# STM32_Schemaic.net
KiCad netlist of a schematic drawn in Altium Designer
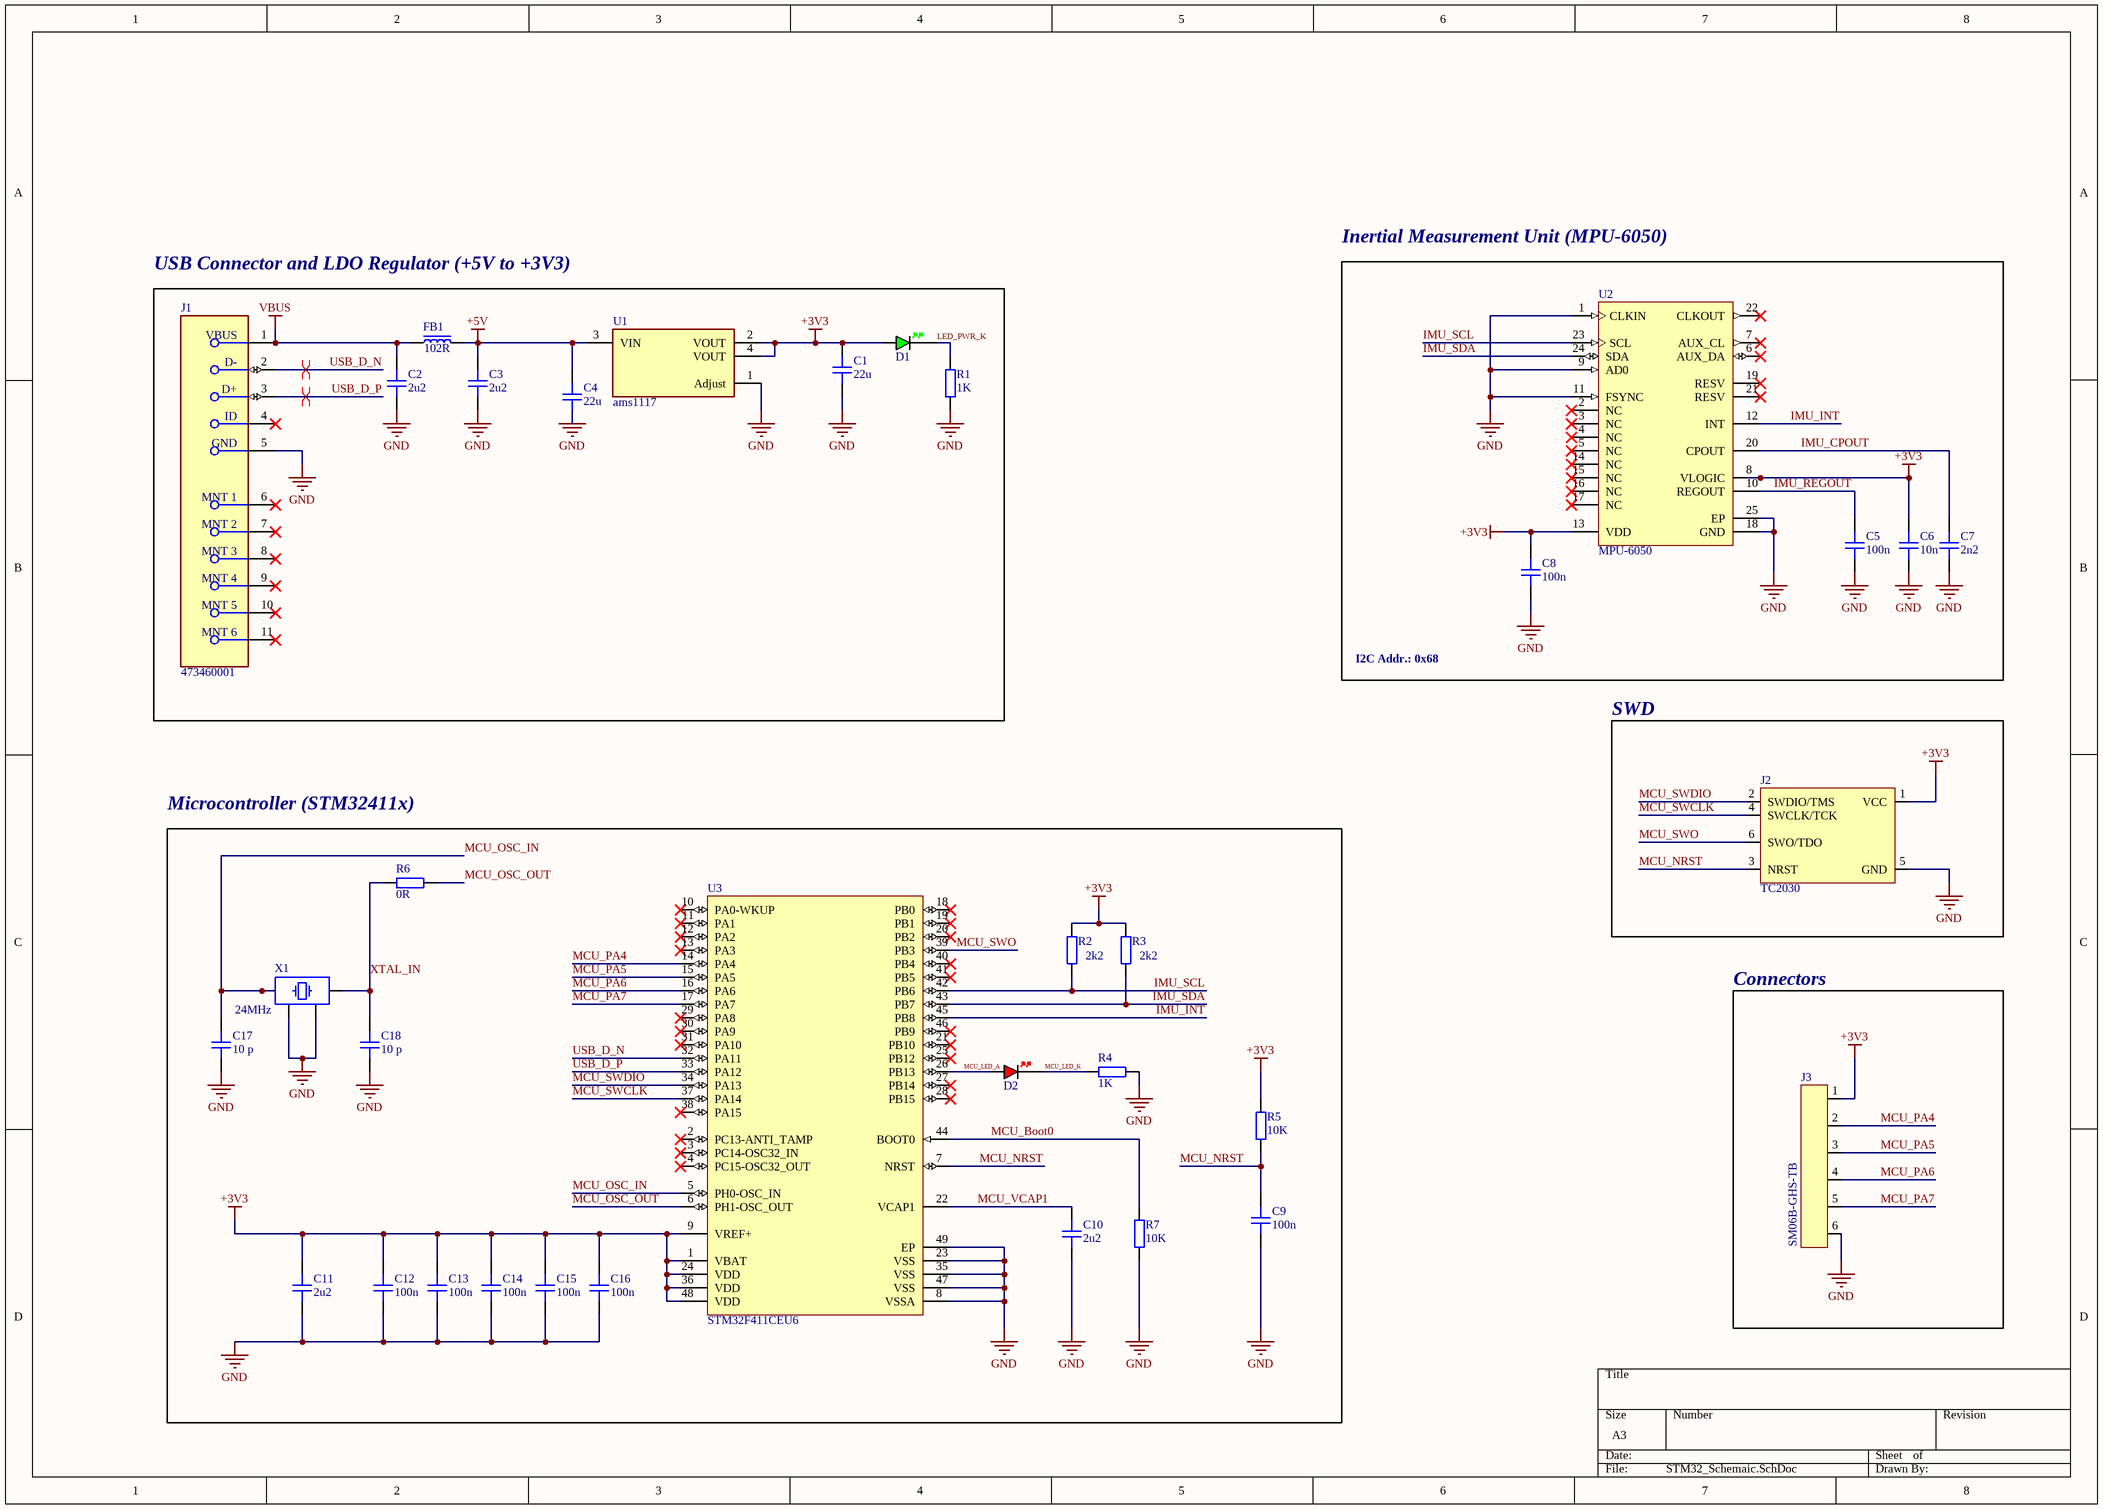
[diagram p0: STM32_Schemaic.SchDoc]

(export (version "E")
  (design (tool "Eeschema 10.0.6"))
  (components
    (comp (ref "C1")
      (value "22u")
      (footprint "CAP_0805")
      (description "Capacitor SMD 0805")
      (libsource (lib "Schematic-Lib-PhilsLab") (part "CAP_0805"))
    )
    (comp (ref "C2")
      (value "2u2")
      (footprint "CAP_0603")
      (description "Capacitor SMD 0603")
      (libsource (lib "Schematic-Lib-PhilsLab") (part "CAP_0603"))
    )
    (comp (ref "C3")
      (value "2u2")
      (footprint "CAP_0603")
      (description "Capacitor SMD 0603")
      (libsource (lib "Schematic-Lib-PhilsLab") (part "CAP_0603"))
    )
    (comp (ref "C4")
      (value "22u")
      (footprint "CAP_0805")
      (description "Capacitor SMD 0805")
      (libsource (lib "Schematic-Lib-PhilsLab") (part "CAP_0805"))
    )
    (comp (ref "C5")
      (value "100n")
      (footprint "CAP_0402")
      (description "Capacitor SMD 0402")
      (libsource (lib "Schematic-Lib-PhilsLab") (part "CAP_0402"))
    )
    (comp (ref "C6")
      (value "10n")
      (footprint "CAP_0402")
      (description "Capacitor SMD 0402")
      (libsource (lib "Schematic-Lib-PhilsLab") (part "CAP_0402"))
    )
    (comp (ref "C7")
      (value "2n2")
      (footprint "CAP_0402")
      (description "Capacitor SMD 0402")
      (libsource (lib "Schematic-Lib-PhilsLab") (part "CAP_0402"))
    )
    (comp (ref "C8")
      (value "100n")
      (footprint "CAP_0402")
      (description "Capacitor SMD 0402")
      (libsource (lib "Schematic-Lib-PhilsLab") (part "CAP_0402"))
    )
    (comp (ref "C9")
      (value "100n")
      (footprint "CAP_0402")
      (description "Capacitor SMD 0402")
      (libsource (lib "Schematic-Lib-PhilsLab") (part "CAP_0402"))
    )
    (comp (ref "C10")
      (value "2u2")
      (footprint "CAP_0603")
      (description "Capacitor SMD 0603")
      (libsource (lib "Schematic-Lib-PhilsLab") (part "CAP_0603"))
    )
    (comp (ref "C11")
      (value "2u2")
      (footprint "CAP_0603")
      (description "Capacitor SMD 0603")
      (libsource (lib "Schematic-Lib-PhilsLab") (part "CAP_0603"))
    )
    (comp (ref "C12")
      (value "100n")
      (footprint "CAP_0402")
      (description "Capacitor SMD 0402")
      (libsource (lib "Schematic-Lib-PhilsLab") (part "CAP_0402"))
    )
    (comp (ref "C13")
      (value "100n")
      (footprint "CAP_0402")
      (description "Capacitor SMD 0402")
      (libsource (lib "Schematic-Lib-PhilsLab") (part "CAP_0402"))
    )
    (comp (ref "C14")
      (value "100n")
      (footprint "CAP_0402")
      (description "Capacitor SMD 0402")
      (libsource (lib "Schematic-Lib-PhilsLab") (part "CAP_0402"))
    )
    (comp (ref "C15")
      (value "100n")
      (footprint "CAP_0402")
      (description "Capacitor SMD 0402")
      (libsource (lib "Schematic-Lib-PhilsLab") (part "CAP_0402"))
    )
    (comp (ref "C16")
      (value "100n")
      (footprint "CAP_0402")
      (description "Capacitor SMD 0402")
      (libsource (lib "Schematic-Lib-PhilsLab") (part "CAP_0402"))
    )
    (comp (ref "C17")
      (value "10 p")
      (footprint "CAP_0402")
      (description "Capacitor SMD 0402")
      (libsource (lib "Schematic-Lib-PhilsLab") (part "CAP_0402"))
    )
    (comp (ref "C18")
      (value "10 p")
      (footprint "CAP_0402")
      (description "Capacitor SMD 0402")
      (libsource (lib "Schematic-Lib-PhilsLab") (part "CAP_0402"))
    )
    (comp (ref "D1")
      (value "GREEN")
      (footprint "LED_0402_GREEN")
      (description "LED 0402 GREEN SMD")
      (libsource (lib "Schematic-Lib-PhilsLab") (part "LED_0402_GREEN"))
    )
    (comp (ref "D2")
      (value "RED")
      (footprint "LED_0402_RED")
      (description "LED 0402 RED SMD")
      (libsource (lib "Schematic-Lib-PhilsLab") (part "LED_0402_RED"))
    )
    (comp (ref "FB1")
      (value "102R")
      (footprint "FB_0603")
      (description "Ferrite Bead SMD 0603")
      (libsource (lib "Schematic-Lib-PhilsLab") (part "FB_0603"))
    )
    (comp (ref "J1")
      (value "473460001")
      (footprint "FP-473460001-MFG")
      (description "CONN RCPT USB2.0 MICRO B SMD R/A")
      (fields
        (field (name "OCTOPART") "https://octopart.com/47346-0001-molex-7164928")
        (field (name "MANUFACTURER") "Molex")
      )
      (libsource (lib "Altium Content Vault") (part "53ae1f1d9b557310b43ca686e5bb76a"))
    )
    (comp (ref "J2")
      (value "TC2030")
      (footprint "TC2030-FP")
      (description "Tag-Connect No-Solder SWD Debug Connector DO NOT PLACE")
      (fields (field (name "MANUFACTURER") "Tag-Connect"))
      (libsource (lib "Schematic-Lib-PhilsLab") (part "TC2030"))
    )
    (comp (ref "J3")
      (value "SM06B-GHS-TB")
      (footprint "SM06B-GHS-TB")
      (description "Header Connector 6 Position 1.25MM Pitch SMD Horizontal JST GH")
      (fields (field (name "MANUFACTURER") "JST"))
      (libsource (lib "Schematic-Lib-PhilsLab") (part "SM06B-GHS-TB"))
    )
    (comp (ref "R1")
      (value "1K")
      (footprint "RES_0402")
      (description "Resistor SMD 0402")
      (libsource (lib "Schematic-Lib-PhilsLab") (part "RES_0402"))
    )
    (comp (ref "R2")
      (value "2k2")
      (footprint "RES_0402")
      (description "Resistor SMD 0402")
      (libsource (lib "Schematic-Lib-PhilsLab") (part "RES_0402"))
    )
    (comp (ref "R3")
      (value "2k2")
      (footprint "RES_0402")
      (description "Resistor SMD 0402")
      (libsource (lib "Schematic-Lib-PhilsLab") (part "RES_0402"))
    )
    (comp (ref "R4")
      (value "1K")
      (footprint "RES_0402")
      (description "Resistor SMD 0402")
      (libsource (lib "Schematic-Lib-PhilsLab") (part "RES_0402"))
    )
    (comp (ref "R5")
      (value "10K")
      (footprint "RES_0402")
      (description "Resistor SMD 0402")
      (libsource (lib "Schematic-Lib-PhilsLab") (part "RES_0402"))
    )
    (comp (ref "R6")
      (value "0R")
      (footprint "RES_0402")
      (description "Resistor SMD 0402")
      (libsource (lib "Schematic-Lib-PhilsLab") (part "RES_0402"))
    )
    (comp (ref "R7")
      (value "10K")
      (footprint "RES_0402")
      (description "Resistor SMD 0402")
      (libsource (lib "Schematic-Lib-PhilsLab") (part "RES_0402"))
    )
    (comp (ref "U1")
      (value "ams1117")
      (footprint "FP-ams1117-IPC_C")
      (description "1A LOW DROPOUT VOLTAGE REGULATOR")
      (libsource (lib "Altium Content Vault") (part "59ad430b93a2c51b3e6ee7c3b069677"))
    )
    (comp (ref "U2")
      (value "MPU-6050")
      (footprint "IS-QFN-24_V")
      (fields (field (name "MANUFACTURER") "InvenSense"))
      (libsource (lib "Altium Content Vault") (part "IS-MPU-6050-QFN-24"))
    )
    (comp (ref "U3")
      (value "STM32F411CEU6")
      (footprint "STM-UFQFPN48_L")
      (libsource (lib "Altium Content Vault") (part "MC-ARM-STM32F411-UFQFPN48"))
    )
    (comp (ref "X1")
      (value "24MHz")
      (footprint "XTAL_3225")
      (description "Crystal SMD 24MHz 10PPM 7pF 3225")
      (fields
        (field (name "MANUFACTURER") "Epson")
        (field (name "MANUFACTURER PART NUMBER") "TSX-3225 24.0000MF15X-AC")
      )
      (libsource (lib "Schematic-Lib-PhilsLab") (part "TSX-3225_24.0000MF15X-AC"))
    )
  )
  (nets
    (net (code "1") (name "+3V3") (class "Default")
      (node (ref "C1") (pin "2") (pinfunction "2_2") (pintype "passive"))
      (node (ref "C11") (pin "2") (pinfunction "2_2") (pintype "passive"))
      (node (ref "C12") (pin "2") (pinfunction "2_2") (pintype "passive"))
      (node (ref "C13") (pin "2") (pinfunction "2_2") (pintype "passive"))
      (node (ref "C14") (pin "2") (pinfunction "2_2") (pintype "passive"))
      (node (ref "C15") (pin "2") (pinfunction "2_2") (pintype "passive"))
      (node (ref "C16") (pin "2") (pinfunction "2_2") (pintype "passive"))
      (node (ref "C6") (pin "2") (pinfunction "2_2") (pintype "passive"))
      (node (ref "C8") (pin "2") (pinfunction "2_2") (pintype "passive"))
      (node (ref "D1") (pin "A") (pinfunction "A_A") (pintype "passive"))
      (node (ref "J2") (pin "1") (pinfunction "VCC_1") (pintype "passive"))
      (node (ref "J3") (pin "1") (pinfunction "1_1") (pintype "passive"))
      (node (ref "R2") (pin "2") (pinfunction "2_2") (pintype "passive"))
      (node (ref "R3") (pin "2") (pinfunction "2_2") (pintype "passive"))
      (node (ref "R5") (pin "2") (pinfunction "2_2") (pintype "passive"))
      (node (ref "U1") (pin "2") (pinfunction "VOUT_2") (pintype "passive"))
      (node (ref "U1") (pin "4") (pinfunction "VOUT_4") (pintype "passive"))
      (node (ref "U2") (pin "13") (pinfunction "VDD_13") (pintype "power_in"))
      (node (ref "U2") (pin "8") (pinfunction "VLOGIC_8") (pintype "power_in"))
      (node (ref "U3") (pin "1") (pinfunction "VBAT_1") (pintype "power_in"))
      (node (ref "U3") (pin "24") (pinfunction "VDD_24") (pintype "power_in"))
      (node (ref "U3") (pin "36") (pinfunction "VDD_36") (pintype "power_in"))
      (node (ref "U3") (pin "48") (pinfunction "VDD_48") (pintype "power_in"))
      (node (ref "U3") (pin "9") (pinfunction "VREF+_9") (pintype "power_in"))
    )
    (net (code "2") (name "+5V") (class "Default")
      (node (ref "C3") (pin "2") (pinfunction "2_2") (pintype "passive"))
      (node (ref "C4") (pin "2") (pinfunction "2_2") (pintype "passive"))
      (node (ref "FB1") (pin "2") (pinfunction "2_2") (pintype "passive"))
      (node (ref "U1") (pin "3") (pinfunction "VIN_3") (pintype "power_in"))
    )
    (net (code "3") (name "/IMU_CPOUT") (class "Default")
      (node (ref "C7") (pin "2") (pinfunction "2_2") (pintype "passive"))
      (node (ref "U2") (pin "20") (pinfunction "CPOUT_20") (pintype "passive"))
    )
    (net (code "4") (name "/IMU_INT") (class "Default")
      (node (ref "U2") (pin "12") (pinfunction "INT_12") (pintype "open_collector"))
      (node (ref "U3") (pin "45") (pinfunction "PB8_45") (pintype "bidirectional"))
    )
    (net (code "5") (name "/IMU_REGOUT") (class "Default")
      (node (ref "C5") (pin "2") (pinfunction "2_2") (pintype "passive"))
      (node (ref "U2") (pin "10") (pinfunction "REGOUT_10") (pintype "passive"))
    )
    (net (code "6") (name "/IMU_SCL") (class "Default")
      (node (ref "R2") (pin "1") (pinfunction "1_1") (pintype "passive"))
      (node (ref "U2") (pin "23") (pinfunction "SCL_23") (pintype "input"))
      (node (ref "U3") (pin "42") (pinfunction "PB6_42") (pintype "bidirectional"))
    )
    (net (code "7") (name "/IMU_SDA") (class "Default")
      (node (ref "R3") (pin "1") (pinfunction "1_1") (pintype "passive"))
      (node (ref "U2") (pin "24") (pinfunction "SDA_24") (pintype "bidirectional"))
      (node (ref "U3") (pin "43") (pinfunction "PB7_43") (pintype "bidirectional"))
    )
    (net (code "8") (name "/LED_PWR_K") (class "Default")
      (node (ref "D1") (pin "K") (pinfunction "K_K") (pintype "passive"))
      (node (ref "R1") (pin "2") (pinfunction "2_2") (pintype "passive"))
    )
    (net (code "9") (name "/MCU_Boot0") (class "Default")
      (node (ref "R7") (pin "2") (pinfunction "2_2") (pintype "passive"))
      (node (ref "U3") (pin "44") (pinfunction "BOOT0_44") (pintype "input"))
    )
    (net (code "10") (name "/MCU_LED_A") (class "Default")
      (node (ref "D2") (pin "A") (pinfunction "A_A") (pintype "passive"))
      (node (ref "U3") (pin "26") (pinfunction "PB13_26") (pintype "bidirectional"))
    )
    (net (code "11") (name "/MCU_LED_K") (class "Default")
      (node (ref "D2") (pin "K") (pinfunction "K_K") (pintype "passive"))
      (node (ref "R4") (pin "2") (pinfunction "2_2") (pintype "passive"))
    )
    (net (code "12") (name "/MCU_NRST") (class "Default")
      (node (ref "C9") (pin "2") (pinfunction "2_2") (pintype "passive"))
      (node (ref "J2") (pin "3") (pinfunction "NRST_3") (pintype "passive"))
      (node (ref "R5") (pin "1") (pinfunction "1_1") (pintype "passive"))
      (node (ref "U3") (pin "7") (pinfunction "NRST_7") (pintype "bidirectional"))
    )
    (net (code "13") (name "/MCU_OSC_IN") (class "Default")
      (node (ref "C17") (pin "2") (pinfunction "2_2") (pintype "passive"))
      (node (ref "U3") (pin "5") (pinfunction "PH0-OSC_IN_5") (pintype "bidirectional"))
      (node (ref "X1") (pin "1") (pinfunction "1_1") (pintype "passive"))
    )
    (net (code "14") (name "/MCU_OSC_OUT") (class "Default")
      (node (ref "R6") (pin "2") (pinfunction "2_2") (pintype "passive"))
      (node (ref "U3") (pin "6") (pinfunction "PH1-OSC_OUT_6") (pintype "bidirectional"))
    )
    (net (code "15") (name "/MCU_PA4") (class "Default")
      (node (ref "J3") (pin "2") (pinfunction "2_2") (pintype "passive"))
      (node (ref "U3") (pin "14") (pinfunction "PA4_14") (pintype "bidirectional"))
    )
    (net (code "16") (name "/MCU_PA5") (class "Default")
      (node (ref "J3") (pin "3") (pinfunction "3_3") (pintype "passive"))
      (node (ref "U3") (pin "15") (pinfunction "PA5_15") (pintype "bidirectional"))
    )
    (net (code "17") (name "/MCU_PA6") (class "Default")
      (node (ref "J3") (pin "4") (pinfunction "4_4") (pintype "passive"))
      (node (ref "U3") (pin "16") (pinfunction "PA6_16") (pintype "bidirectional"))
    )
    (net (code "18") (name "/MCU_PA7") (class "Default")
      (node (ref "J3") (pin "5") (pinfunction "5_5") (pintype "passive"))
      (node (ref "U3") (pin "17") (pinfunction "PA7_17") (pintype "bidirectional"))
    )
    (net (code "19") (name "/MCU_SWCLK") (class "Default")
      (node (ref "J2") (pin "4") (pinfunction "SWCLK/TCK_4") (pintype "passive"))
      (node (ref "U3") (pin "37") (pinfunction "PA14_37") (pintype "bidirectional"))
    )
    (net (code "20") (name "/MCU_SWDIO") (class "Default")
      (node (ref "J2") (pin "2") (pinfunction "SWDIO/TMS_2") (pintype "passive"))
      (node (ref "U3") (pin "34") (pinfunction "PA13_34") (pintype "bidirectional"))
    )
    (net (code "21") (name "/MCU_SWO") (class "Default")
      (node (ref "J2") (pin "6") (pinfunction "SWO/TDO_6") (pintype "passive"))
      (node (ref "U3") (pin "39") (pinfunction "PB3_39") (pintype "bidirectional"))
    )
    (net (code "22") (name "/MCU_VCAP1") (class "Default")
      (node (ref "C10") (pin "2") (pinfunction "2_2") (pintype "passive"))
      (node (ref "U3") (pin "22") (pinfunction "VCAP1_22") (pintype "passive"))
    )
    (net (code "23") (name "/USB_D_N") (class "Default")
      (node (ref "J1") (pin "2") (pinfunction "D-_2") (pintype "bidirectional"))
      (node (ref "U3") (pin "32") (pinfunction "PA11_32") (pintype "bidirectional"))
    )
    (net (code "24") (name "/USB_D_P") (class "Default")
      (node (ref "J1") (pin "3") (pinfunction "D+_3") (pintype "bidirectional"))
      (node (ref "U3") (pin "33") (pinfunction "PA12_33") (pintype "bidirectional"))
    )
    (net (code "25") (name "/XTAL_IN") (class "Default")
      (node (ref "C18") (pin "2") (pinfunction "2_2") (pintype "passive"))
      (node (ref "R6") (pin "1") (pinfunction "1_1") (pintype "passive"))
      (node (ref "X1") (pin "3") (pinfunction "3_3") (pintype "passive"))
    )
    (net (code "26") (name "GND") (class "Default")
      (node (ref "C1") (pin "1") (pinfunction "1_1") (pintype "passive"))
      (node (ref "C10") (pin "1") (pinfunction "1_1") (pintype "passive"))
      (node (ref "C11") (pin "1") (pinfunction "1_1") (pintype "passive"))
      (node (ref "C12") (pin "1") (pinfunction "1_1") (pintype "passive"))
      (node (ref "C13") (pin "1") (pinfunction "1_1") (pintype "passive"))
      (node (ref "C14") (pin "1") (pinfunction "1_1") (pintype "passive"))
      (node (ref "C15") (pin "1") (pinfunction "1_1") (pintype "passive"))
      (node (ref "C16") (pin "1") (pinfunction "1_1") (pintype "passive"))
      (node (ref "C17") (pin "1") (pinfunction "1_1") (pintype "passive"))
      (node (ref "C18") (pin "1") (pinfunction "1_1") (pintype "passive"))
      (node (ref "C2") (pin "1") (pinfunction "1_1") (pintype "passive"))
      (node (ref "C3") (pin "1") (pinfunction "1_1") (pintype "passive"))
      (node (ref "C4") (pin "1") (pinfunction "1_1") (pintype "passive"))
      (node (ref "C5") (pin "1") (pinfunction "1_1") (pintype "passive"))
      (node (ref "C6") (pin "1") (pinfunction "1_1") (pintype "passive"))
      (node (ref "C7") (pin "1") (pinfunction "1_1") (pintype "passive"))
      (node (ref "C8") (pin "1") (pinfunction "1_1") (pintype "passive"))
      (node (ref "C9") (pin "1") (pinfunction "1_1") (pintype "passive"))
      (node (ref "J1") (pin "5") (pinfunction "GND_5") (pintype "power_in"))
      (node (ref "J2") (pin "5") (pinfunction "GND_5") (pintype "passive"))
      (node (ref "J3") (pin "6") (pinfunction "6_6") (pintype "passive"))
      (node (ref "R1") (pin "1") (pinfunction "1_1") (pintype "passive"))
      (node (ref "R4") (pin "1") (pinfunction "1_1") (pintype "passive"))
      (node (ref "R7") (pin "1") (pinfunction "1_1") (pintype "passive"))
      (node (ref "U1") (pin "1") (pinfunction "Adjust_1") (pintype "passive"))
      (node (ref "U2") (pin "1") (pinfunction "CLKIN_1") (pintype "input"))
      (node (ref "U2") (pin "11") (pinfunction "FSYNC_11") (pintype "input"))
      (node (ref "U2") (pin "18") (pinfunction "GND_18") (pintype "power_in"))
      (node (ref "U2") (pin "25") (pinfunction "EP_25") (pintype "power_in"))
      (node (ref "U2") (pin "9") (pinfunction "AD0_9") (pintype "input"))
      (node (ref "U3") (pin "23") (pinfunction "VSS_23") (pintype "power_in"))
      (node (ref "U3") (pin "35") (pinfunction "VSS_35") (pintype "power_in"))
      (node (ref "U3") (pin "47") (pinfunction "VSS_47") (pintype "power_in"))
      (node (ref "U3") (pin "49") (pinfunction "EP_49") (pintype "power_in"))
      (node (ref "U3") (pin "8") (pinfunction "VSSA_8") (pintype "power_in"))
      (node (ref "X1") (pin "2") (pinfunction "2_2") (pintype "passive"))
      (node (ref "X1") (pin "4") (pinfunction "4_4") (pintype "passive"))
    )
    (net (code "27") (name "VBUS") (class "Default")
      (node (ref "C2") (pin "2") (pinfunction "2_2") (pintype "passive"))
      (node (ref "FB1") (pin "1") (pinfunction "1_1") (pintype "passive"))
      (node (ref "J1") (pin "1") (pinfunction "VBUS_1") (pintype "power_in"))
    )
    (net (code "28") (name "unconnected-(J1-ID-Pad4)") (class "Default")
      (node (ref "J1") (pin "4") (pinfunction "ID_4") (pintype "passive+no_connect"))
    )
    (net (code "29") (name "unconnected-(J1-MNT_1-Pad6)") (class "Default")
      (node (ref "J1") (pin "6") (pinfunction "MNT_1_6") (pintype "passive+no_connect"))
    )
    (net (code "30") (name "unconnected-(J1-MNT_2-Pad7)") (class "Default")
      (node (ref "J1") (pin "7") (pinfunction "MNT_2_7") (pintype "passive+no_connect"))
    )
    (net (code "31") (name "unconnected-(J1-MNT_3-Pad8)") (class "Default")
      (node (ref "J1") (pin "8") (pinfunction "MNT_3_8") (pintype "passive+no_connect"))
    )
    (net (code "32") (name "unconnected-(J1-MNT_4-Pad9)") (class "Default")
      (node (ref "J1") (pin "9") (pinfunction "MNT_4_9") (pintype "passive+no_connect"))
    )
    (net (code "33") (name "unconnected-(J1-MNT_5-Pad10)") (class "Default")
      (node (ref "J1") (pin "10") (pinfunction "MNT_5_10") (pintype "passive+no_connect"))
    )
    (net (code "34") (name "unconnected-(J1-MNT_6-Pad11)") (class "Default")
      (node (ref "J1") (pin "11") (pinfunction "MNT_6_11") (pintype "passive+no_connect"))
    )
    (net (code "35") (name "unconnected-(U2-AUX_CL-Pad7)") (class "Default")
      (node (ref "U2") (pin "7") (pinfunction "AUX_CL_7") (pintype "output+no_connect"))
    )
    (net (code "36") (name "unconnected-(U2-AUX_DA-Pad6)") (class "Default")
      (node (ref "U2") (pin "6") (pinfunction "AUX_DA_6") (pintype "bidirectional+no_connect"))
    )
    (net (code "37") (name "unconnected-(U2-CLKOUT-Pad22)") (class "Default")
      (node (ref "U2") (pin "22") (pinfunction "CLKOUT_22") (pintype "output+no_connect"))
    )
    (net (code "38") (name "unconnected-(U2-NC-Pad2)") (class "Default")
      (node (ref "U2") (pin "2") (pinfunction "NC_2") (pintype "passive+no_connect"))
    )
    (net (code "39") (name "unconnected-(U2-NC-Pad3)") (class "Default")
      (node (ref "U2") (pin "3") (pinfunction "NC_3") (pintype "passive+no_connect"))
    )
    (net (code "40") (name "unconnected-(U2-NC-Pad4)") (class "Default")
      (node (ref "U2") (pin "4") (pinfunction "NC_4") (pintype "passive+no_connect"))
    )
    (net (code "41") (name "unconnected-(U2-NC-Pad5)") (class "Default")
      (node (ref "U2") (pin "5") (pinfunction "NC_5") (pintype "passive+no_connect"))
    )
    (net (code "42") (name "unconnected-(U2-NC-Pad14)") (class "Default")
      (node (ref "U2") (pin "14") (pinfunction "NC_14") (pintype "passive+no_connect"))
    )
    (net (code "43") (name "unconnected-(U2-NC-Pad15)") (class "Default")
      (node (ref "U2") (pin "15") (pinfunction "NC_15") (pintype "passive+no_connect"))
    )
    (net (code "44") (name "unconnected-(U2-NC-Pad16)") (class "Default")
      (node (ref "U2") (pin "16") (pinfunction "NC_16") (pintype "passive+no_connect"))
    )
    (net (code "45") (name "unconnected-(U2-NC-Pad17)") (class "Default")
      (node (ref "U2") (pin "17") (pinfunction "NC_17") (pintype "passive+no_connect"))
    )
    (net (code "46") (name "unconnected-(U2-RESV-Pad19)") (class "Default")
      (node (ref "U2") (pin "19") (pinfunction "RESV_19") (pintype "passive+no_connect"))
    )
    (net (code "47") (name "unconnected-(U2-RESV-Pad21)") (class "Default")
      (node (ref "U2") (pin "21") (pinfunction "RESV_21") (pintype "passive+no_connect"))
    )
    (net (code "48") (name "unconnected-(U3-PA0-WKUP-Pad10)") (class "Default")
      (node (ref "U3") (pin "10") (pinfunction "PA0-WKUP_10") (pintype "bidirectional+no_connect"))
    )
    (net (code "49") (name "unconnected-(U3-PA1-Pad11)") (class "Default")
      (node (ref "U3") (pin "11") (pinfunction "PA1_11") (pintype "bidirectional+no_connect"))
    )
    (net (code "50") (name "unconnected-(U3-PA2-Pad12)") (class "Default")
      (node (ref "U3") (pin "12") (pinfunction "PA2_12") (pintype "bidirectional+no_connect"))
    )
    (net (code "51") (name "unconnected-(U3-PA3-Pad13)") (class "Default")
      (node (ref "U3") (pin "13") (pinfunction "PA3_13") (pintype "bidirectional+no_connect"))
    )
    (net (code "52") (name "unconnected-(U3-PA8-Pad29)") (class "Default")
      (node (ref "U3") (pin "29") (pinfunction "PA8_29") (pintype "bidirectional+no_connect"))
    )
    (net (code "53") (name "unconnected-(U3-PA9-Pad30)") (class "Default")
      (node (ref "U3") (pin "30") (pinfunction "PA9_30") (pintype "bidirectional+no_connect"))
    )
    (net (code "54") (name "unconnected-(U3-PA10-Pad31)") (class "Default")
      (node (ref "U3") (pin "31") (pinfunction "PA10_31") (pintype "bidirectional+no_connect"))
    )
    (net (code "55") (name "unconnected-(U3-PA15-Pad38)") (class "Default")
      (node (ref "U3") (pin "38") (pinfunction "PA15_38") (pintype "bidirectional+no_connect"))
    )
    (net (code "56") (name "unconnected-(U3-PB0-Pad18)") (class "Default")
      (node (ref "U3") (pin "18") (pinfunction "PB0_18") (pintype "bidirectional+no_connect"))
    )
    (net (code "57") (name "unconnected-(U3-PB1-Pad19)") (class "Default")
      (node (ref "U3") (pin "19") (pinfunction "PB1_19") (pintype "bidirectional+no_connect"))
    )
    (net (code "58") (name "unconnected-(U3-PB2-Pad20)") (class "Default")
      (node (ref "U3") (pin "20") (pinfunction "PB2_20") (pintype "bidirectional+no_connect"))
    )
    (net (code "59") (name "unconnected-(U3-PB4-Pad40)") (class "Default")
      (node (ref "U3") (pin "40") (pinfunction "PB4_40") (pintype "bidirectional+no_connect"))
    )
    (net (code "60") (name "unconnected-(U3-PB5-Pad41)") (class "Default")
      (node (ref "U3") (pin "41") (pinfunction "PB5_41") (pintype "bidirectional+no_connect"))
    )
    (net (code "61") (name "unconnected-(U3-PB9-Pad46)") (class "Default")
      (node (ref "U3") (pin "46") (pinfunction "PB9_46") (pintype "bidirectional+no_connect"))
    )
    (net (code "62") (name "unconnected-(U3-PB10-Pad21)") (class "Default")
      (node (ref "U3") (pin "21") (pinfunction "PB10_21") (pintype "bidirectional+no_connect"))
    )
    (net (code "63") (name "unconnected-(U3-PB12-Pad25)") (class "Default")
      (node (ref "U3") (pin "25") (pinfunction "PB12_25") (pintype "bidirectional+no_connect"))
    )
    (net (code "64") (name "unconnected-(U3-PB14-Pad27)") (class "Default")
      (node (ref "U3") (pin "27") (pinfunction "PB14_27") (pintype "bidirectional+no_connect"))
    )
    (net (code "65") (name "unconnected-(U3-PB15-Pad28)") (class "Default")
      (node (ref "U3") (pin "28") (pinfunction "PB15_28") (pintype "bidirectional+no_connect"))
    )
    (net (code "66") (name "unconnected-(U3-PC13-ANTI_TAMP-Pad2)") (class "Default")
      (node (ref "U3") (pin "2") (pinfunction "PC13-ANTI_TAMP_2") (pintype "bidirectional+no_connect"))
    )
    (net (code "67") (name "unconnected-(U3-PC14-OSC32_IN-Pad3)") (class "Default")
      (node (ref "U3") (pin "3") (pinfunction "PC14-OSC32_IN_3") (pintype "bidirectional+no_connect"))
    )
    (net (code "68") (name "unconnected-(U3-PC15-OSC32_OUT-Pad4)") (class "Default")
      (node (ref "U3") (pin "4") (pinfunction "PC15-OSC32_OUT_4") (pintype "bidirectional+no_connect"))
    )
  )
)
